# pcswtich.net
KiCad netlist of a schematic drawn in EAGLE
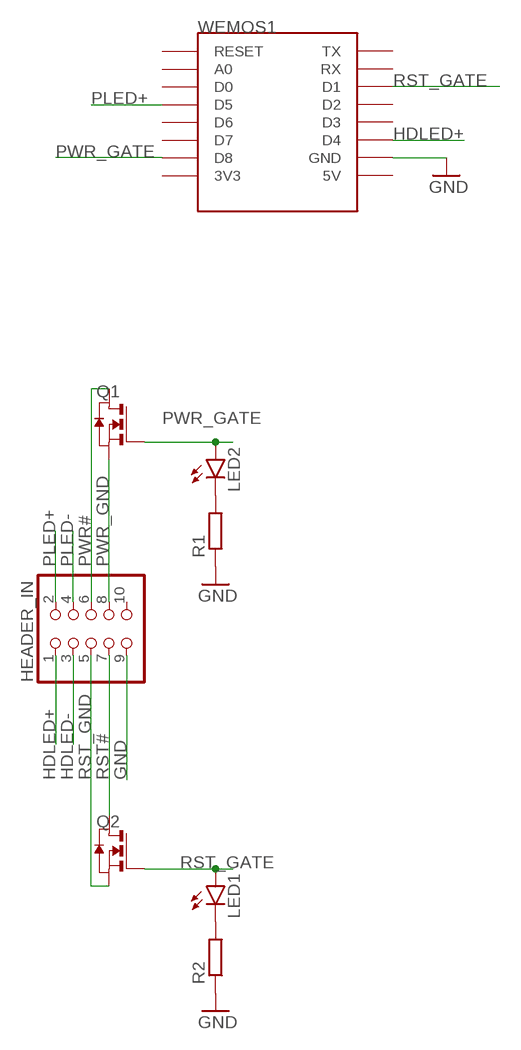
[diagram p0: schematic, sheet 1]

(export (version "E")
  (design (tool "Eeschema 10.0.6"))
  (components
    (comp (ref "HEADER_IN")
      (value "PINHD-2X5")
      (footprint "eagle-import:2X05")
      (libsource (lib "eagle-import") (part "PINHD-2X5"))
    )
    (comp (ref "LED1")
      (value "LEDCHIPLED_0805")
      (footprint "eagle-import:CHIPLED_0805")
      (libsource (lib "eagle-import") (part "LEDCHIPLED_0805"))
    )
    (comp (ref "LED2")
      (value "LEDCHIPLED_0805")
      (footprint "eagle-import:CHIPLED_0805")
      (libsource (lib "eagle-import") (part "LEDCHIPLED_0805"))
    )
    (comp (ref "Q1")
      (value "NMOSSOT23")
      (footprint "eagle-import:SOT-23")
      (libsource (lib "eagle-import") (part "NMOSSOT23"))
    )
    (comp (ref "Q2")
      (value "NMOSSOT23")
      (footprint "eagle-import:SOT-23")
      (libsource (lib "eagle-import") (part "NMOSSOT23"))
    )
    (comp (ref "R1")
      (value "R-EU_R0805")
      (footprint "eagle-import:R0805")
      (libsource (lib "eagle-import") (part "R-EU_R0805"))
    )
    (comp (ref "R2")
      (value "R-EU_R0805")
      (footprint "eagle-import:R0805")
      (libsource (lib "eagle-import") (part "R-EU_R0805"))
    )
    (comp (ref "WEMOS1")
      (value "WEMOS-D1-MINI")
      (footprint "eagle-import:WEMOS-D1-MINI")
      (libsource (lib "eagle-import") (part "WEMOS-D1-MINI"))
    )
  )
  (nets
    (net (code "1") (name "/HDLED+") (class "Default")
      (node (ref "HEADER_IN") (pin "1") (pinfunction "1_1") (pintype "passive"))
      (node (ref "WEMOS1") (pin "D4") (pinfunction "D4_D4") (pintype "bidirectional"))
    )
    (net (code "2") (name "/HDLED-") (class "Default")
      (node (ref "HEADER_IN") (pin "3") (pinfunction "3_3") (pintype "passive"))
    )
    (net (code "3") (name "/PLED+") (class "Default")
      (node (ref "HEADER_IN") (pin "2") (pinfunction "2_2") (pintype "passive"))
      (node (ref "WEMOS1") (pin "D5") (pinfunction "D5_D5") (pintype "bidirectional"))
    )
    (net (code "4") (name "/PLED-") (class "Default")
      (node (ref "HEADER_IN") (pin "4") (pinfunction "4_4") (pintype "passive"))
    )
    (net (code "5") (name "/PWR#") (class "Default")
      (node (ref "HEADER_IN") (pin "6") (pinfunction "6_6") (pintype "passive"))
      (node (ref "Q1") (pin "1") (pinfunction "D_1") (pintype "passive"))
    )
    (net (code "6") (name "/PWR_GATE") (class "Default")
      (node (ref "LED2") (pin "A") (pinfunction "A_A") (pintype "passive"))
      (node (ref "Q1") (pin "3") (pinfunction "G_3") (pintype "passive"))
      (node (ref "WEMOS1") (pin "D8") (pinfunction "D8_D8") (pintype "bidirectional"))
    )
    (net (code "7") (name "/PWR_GND") (class "Default")
      (node (ref "HEADER_IN") (pin "8") (pinfunction "8_8") (pintype "passive"))
      (node (ref "Q1") (pin "2") (pinfunction "S_2") (pintype "passive"))
    )
    (net (code "8") (name "/RST#") (class "Default")
      (node (ref "HEADER_IN") (pin "7") (pinfunction "7_7") (pintype "passive"))
      (node (ref "Q2") (pin "1") (pinfunction "D_1") (pintype "passive"))
    )
    (net (code "9") (name "/RST_GATE") (class "Default")
      (node (ref "LED1") (pin "A") (pinfunction "A_A") (pintype "passive"))
      (node (ref "Q2") (pin "3") (pinfunction "G_3") (pintype "passive"))
      (node (ref "WEMOS1") (pin "D1") (pinfunction "D1_D1") (pintype "bidirectional"))
    )
    (net (code "10") (name "/RST_GND") (class "Default")
      (node (ref "HEADER_IN") (pin "5") (pinfunction "5_5") (pintype "passive"))
      (node (ref "Q2") (pin "2") (pinfunction "S_2") (pintype "passive"))
    )
    (net (code "11") (name "GND") (class "Default")
      (node (ref "HEADER_IN") (pin "9") (pinfunction "9_9") (pintype "passive"))
      (node (ref "R1") (pin "1") (pinfunction "1_1") (pintype "passive"))
      (node (ref "R2") (pin "1") (pinfunction "1_1") (pintype "passive"))
      (node (ref "WEMOS1") (pin "GND") (pinfunction "GND_GND") (pintype "bidirectional"))
    )
    (net (code "12") (name "Net-(LED1-PadC)") (class "Default")
      (node (ref "LED1") (pin "C") (pinfunction "C_C") (pintype "passive"))
      (node (ref "R2") (pin "2") (pinfunction "2_2") (pintype "passive"))
    )
    (net (code "13") (name "Net-(LED2-PadC)") (class "Default")
      (node (ref "LED2") (pin "C") (pinfunction "C_C") (pintype "passive"))
      (node (ref "R1") (pin "2") (pinfunction "2_2") (pintype "passive"))
    )
    (net (code "14") (name "unconnected-(HEADER_IN-Pad10)") (class "Default")
      (node (ref "HEADER_IN") (pin "10") (pinfunction "10_10") (pintype "passive"))
    )
    (net (code "15") (name "unconnected-(WEMOS1-Pad3V3)") (class "Default")
      (node (ref "WEMOS1") (pin "3V3") (pinfunction "3V3_3V3") (pintype "bidirectional"))
    )
    (net (code "16") (name "unconnected-(WEMOS1-Pad5V)") (class "Default")
      (node (ref "WEMOS1") (pin "5V") (pinfunction "5V_5V") (pintype "bidirectional"))
    )
    (net (code "17") (name "unconnected-(WEMOS1-PadA0)") (class "Default")
      (node (ref "WEMOS1") (pin "A0") (pinfunction "A0_A0") (pintype "bidirectional"))
    )
    (net (code "18") (name "unconnected-(WEMOS1-PadD0)") (class "Default")
      (node (ref "WEMOS1") (pin "D0") (pinfunction "D0_D0") (pintype "bidirectional"))
    )
    (net (code "19") (name "unconnected-(WEMOS1-PadD2)") (class "Default")
      (node (ref "WEMOS1") (pin "D2") (pinfunction "D2_D2") (pintype "bidirectional"))
    )
    (net (code "20") (name "unconnected-(WEMOS1-PadD3)") (class "Default")
      (node (ref "WEMOS1") (pin "D3") (pinfunction "D3_D3") (pintype "bidirectional"))
    )
    (net (code "21") (name "unconnected-(WEMOS1-PadD6)") (class "Default")
      (node (ref "WEMOS1") (pin "D6") (pinfunction "D6_D6") (pintype "bidirectional"))
    )
    (net (code "22") (name "unconnected-(WEMOS1-PadD7)") (class "Default")
      (node (ref "WEMOS1") (pin "D7") (pinfunction "D7_D7") (pintype "bidirectional"))
    )
    (net (code "23") (name "unconnected-(WEMOS1-PadRESET)") (class "Default")
      (node (ref "WEMOS1") (pin "RESET") (pinfunction "RESET_RESET") (pintype "bidirectional"))
    )
    (net (code "24") (name "unconnected-(WEMOS1-PadRX)") (class "Default")
      (node (ref "WEMOS1") (pin "RX") (pinfunction "RX_RX") (pintype "bidirectional"))
    )
    (net (code "25") (name "unconnected-(WEMOS1-PadTX)") (class "Default")
      (node (ref "WEMOS1") (pin "TX") (pinfunction "TX_TX") (pintype "bidirectional"))
    )
  )
)
